# ArdNixie.net
KiCad netlist of a schematic drawn in EAGLE
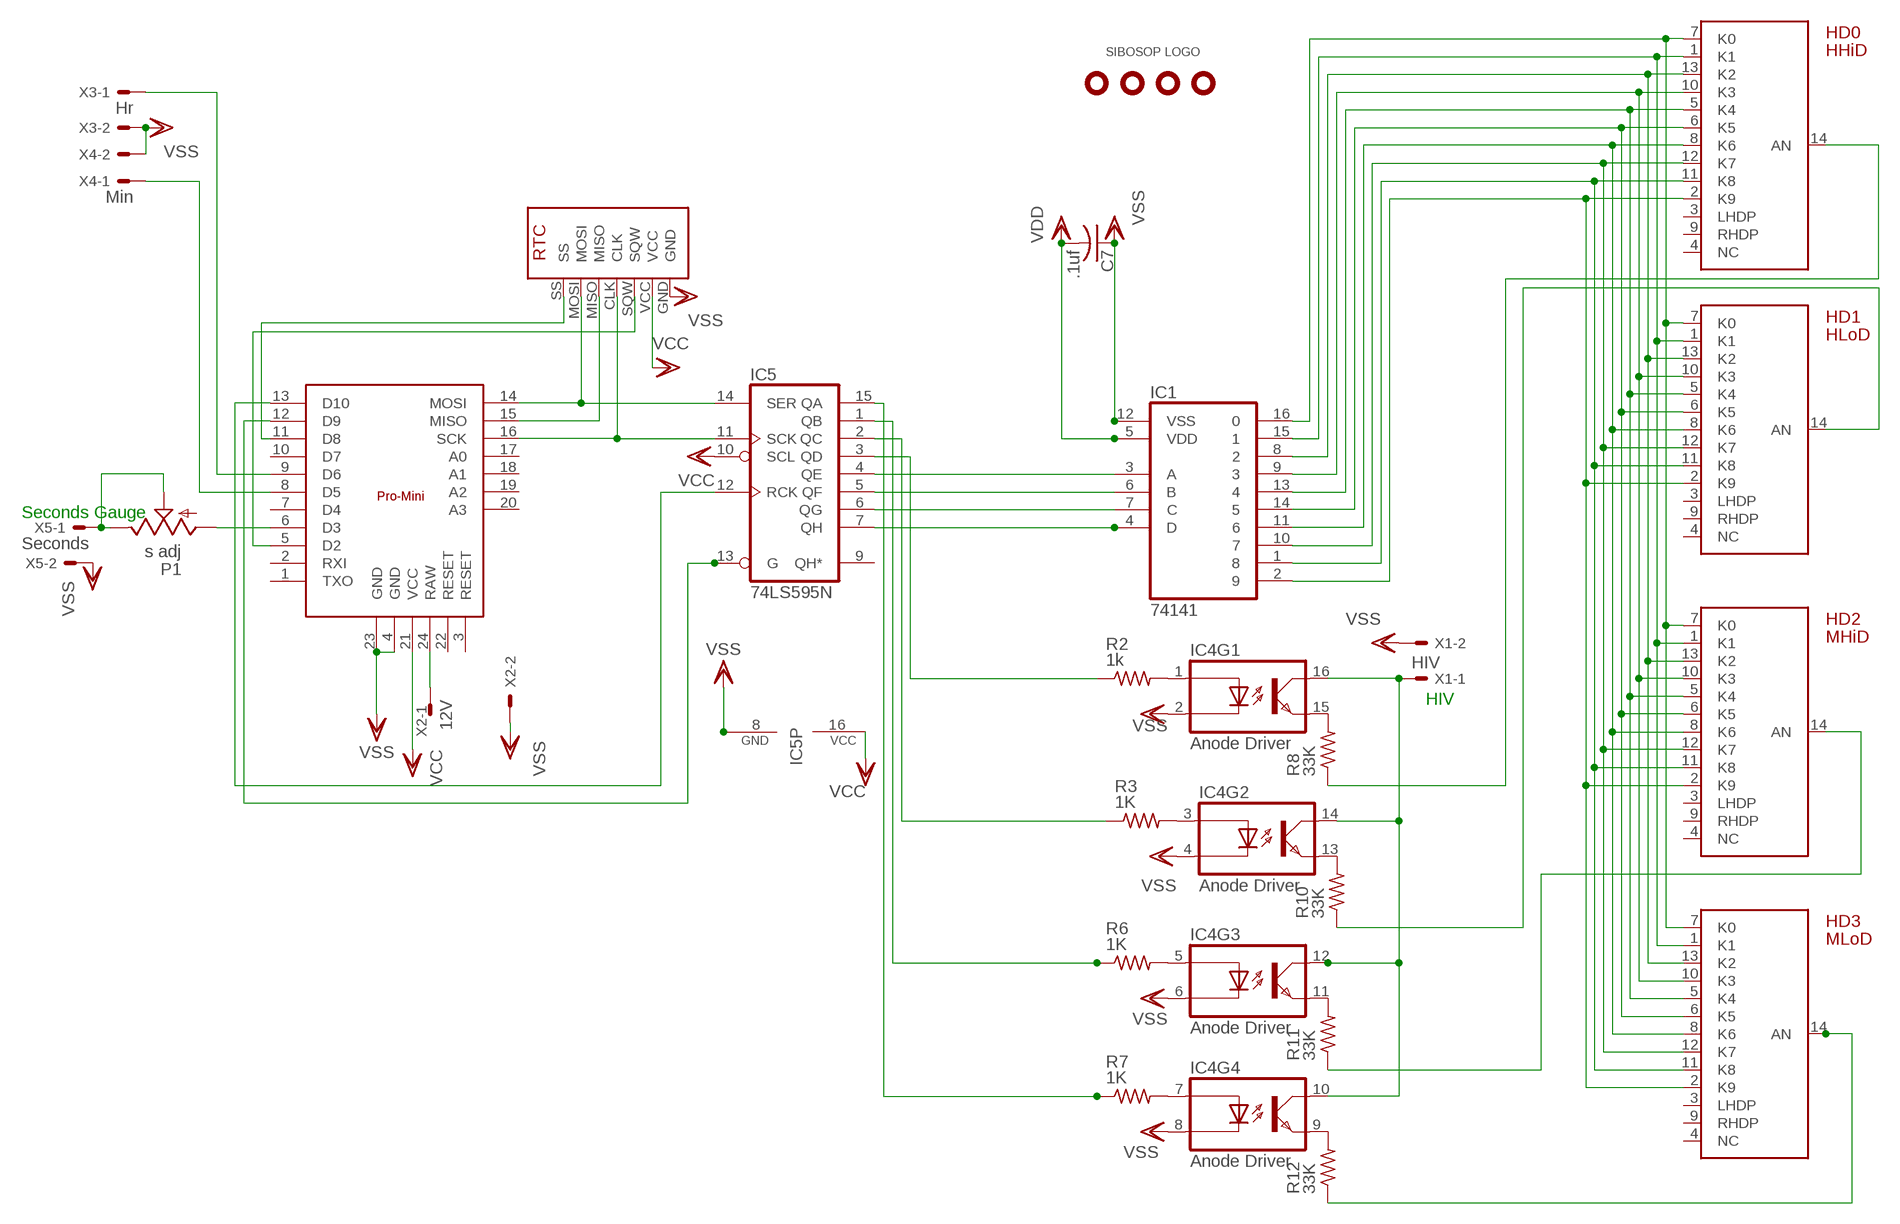
[diagram p0: schematic, sheet 1]

(export (version "E")
  (design (tool "Eeschema 10.0.6"))
  (components
    (comp (ref "C7")
      (value ".1uf")
      (footprint "eagle-import:C025-024X044")
      (libsource (lib "eagle-import") (part "C-US025-024X044"))
    )
    (comp (ref "HD0")
      (value "HHiD")
      (footprint "eagle-import:DIL14")
      (libsource (lib "eagle-import") (part "NIXIE-5440-HEADER"))
    )
    (comp (ref "HD1")
      (value "HLoD")
      (footprint "eagle-import:DIL14")
      (libsource (lib "eagle-import") (part "NIXIE-5440-HEADER"))
    )
    (comp (ref "HD2")
      (value "MHiD")
      (footprint "eagle-import:DIL14")
      (libsource (lib "eagle-import") (part "NIXIE-5440-HEADER"))
    )
    (comp (ref "HD3")
      (value "MLoD")
      (footprint "eagle-import:DIL14")
      (libsource (lib "eagle-import") (part "NIXIE-5440-HEADER"))
    )
    (comp (ref "IC1")
      (value "74141")
      (footprint "eagle-import:DIP16")
      (libsource (lib "eagle-import") (part "74141"))
    )
    (comp (ref "IC2")
      (value "PRO-MINI")
      (footprint "eagle-import:DIL24-6-EXT")
      (libsource (lib "eagle-import") (part "PRO-MINI"))
    )
    (comp (ref "IC3")
      (value "SPARKRTC")
      (footprint "eagle-import:SPARKRTC")
      (libsource (lib "eagle-import") (part "SPARKRTC"))
    )
    (comp (ref "IC4")
      (value "Anode Driver")
      (footprint "eagle-import:DIP16")
      (libsource (lib "eagle-import") (part "TLP627"))
    )
    (comp (ref "IC5")
      (value "74LS595N")
      (footprint "eagle-import:DIL16")
      (libsource (lib "eagle-import") (part "74595NLS"))
    )
    (comp (ref "P1")
      (value "s adj")
      (footprint "eagle-import:RJ6S")
      (libsource (lib "eagle-import") (part "TRIMPOT"))
    )
    (comp (ref "R2")
      (value "1k")
      (footprint "eagle-import:0204V")
      (libsource (lib "eagle-import") (part "R-US_0204/2V"))
    )
    (comp (ref "R3")
      (value "1K")
      (footprint "eagle-import:0204V")
      (libsource (lib "eagle-import") (part "R-US_0204/2V"))
    )
    (comp (ref "R6")
      (value "1K")
      (footprint "eagle-import:0204V")
      (libsource (lib "eagle-import") (part "R-US_0204/2V"))
    )
    (comp (ref "R7")
      (value "1K")
      (footprint "eagle-import:0204V")
      (libsource (lib "eagle-import") (part "R-US_0204/2V"))
    )
    (comp (ref "R8")
      (value "33K")
      (footprint "eagle-import:0204V")
      (libsource (lib "eagle-import") (part "R-US_0204/2V"))
    )
    (comp (ref "R10")
      (value "33K")
      (footprint "eagle-import:0204V")
      (libsource (lib "eagle-import") (part "R-US_0204/2V"))
    )
    (comp (ref "R11")
      (value "33K")
      (footprint "eagle-import:0204V")
      (libsource (lib "eagle-import") (part "R-US_0204/2V"))
    )
    (comp (ref "R12")
      (value "33K")
      (footprint "eagle-import:0204V")
      (libsource (lib "eagle-import") (part "R-US_0204/2V"))
    )
    (comp (ref "U$1")
      (value "HOLE-125")
      (footprint "eagle-import:HOLE-125")
      (libsource (lib "eagle-import") (part "HOLE-125"))
    )
    (comp (ref "U$2")
      (value "HOLE-125")
      (footprint "eagle-import:HOLE-125")
      (libsource (lib "eagle-import") (part "HOLE-125"))
    )
    (comp (ref "U$3")
      (value "LOGO")
      (footprint "eagle-import:LOGO")
      (libsource (lib "eagle-import") (part "LOGO"))
    )
    (comp (ref "U$5")
      (value "HOLE-125")
      (footprint "eagle-import:HOLE-125")
      (libsource (lib "eagle-import") (part "HOLE-125"))
    )
    (comp (ref "U$7")
      (value "HOLE-125")
      (footprint "eagle-import:HOLE-125")
      (libsource (lib "eagle-import") (part "HOLE-125"))
    )
    (comp (ref "X1")
      (value "HIV")
      (footprint "eagle-import:22-23-2021")
      (libsource (lib "eagle-import") (part "22-23-2021"))
    )
    (comp (ref "X2")
      (value "12V")
      (footprint "eagle-import:22-23-2021")
      (libsource (lib "eagle-import") (part "22-23-2021"))
    )
    (comp (ref "X3")
      (value "Hr")
      (footprint "eagle-import:22-23-2021")
      (libsource (lib "eagle-import") (part "22-23-2021"))
    )
    (comp (ref "X4")
      (value "Min")
      (footprint "eagle-import:22-23-2021")
      (libsource (lib "eagle-import") (part "22-23-2021"))
    )
    (comp (ref "X5")
      (value "Seconds")
      (footprint "eagle-import:22-23-2021")
      (libsource (lib "eagle-import") (part "22-23-2021"))
    )
  )
  (nets
    (net (code "1") (name "Net-(HD0-AN)") (class "Default")
      (node (ref "HD0") (pin "14") (pinfunction "AN_14") (pintype "passive"))
      (node (ref "R8") (pin "1") (pinfunction "1_1") (pintype "passive"))
    )
    (net (code "2") (name "Net-(HD0-K0)") (class "Default")
      (node (ref "HD0") (pin "7") (pinfunction "K0_7") (pintype "passive"))
      (node (ref "HD1") (pin "7") (pinfunction "K0_7") (pintype "passive"))
      (node (ref "HD2") (pin "7") (pinfunction "K0_7") (pintype "passive"))
      (node (ref "HD3") (pin "7") (pinfunction "K0_7") (pintype "passive"))
      (node (ref "IC1") (pin "16") (pinfunction "0_16") (pintype "open_collector"))
    )
    (net (code "3") (name "Net-(HD0-K1)") (class "Default")
      (node (ref "HD0") (pin "1") (pinfunction "K1_1") (pintype "passive"))
      (node (ref "HD1") (pin "1") (pinfunction "K1_1") (pintype "passive"))
      (node (ref "HD2") (pin "1") (pinfunction "K1_1") (pintype "passive"))
      (node (ref "HD3") (pin "1") (pinfunction "K1_1") (pintype "passive"))
      (node (ref "IC1") (pin "15") (pinfunction "1_15") (pintype "open_collector"))
    )
    (net (code "4") (name "Net-(HD0-K2)") (class "Default")
      (node (ref "HD0") (pin "13") (pinfunction "K2_13") (pintype "passive"))
      (node (ref "HD1") (pin "13") (pinfunction "K2_13") (pintype "passive"))
      (node (ref "HD2") (pin "13") (pinfunction "K2_13") (pintype "passive"))
      (node (ref "HD3") (pin "13") (pinfunction "K2_13") (pintype "passive"))
      (node (ref "IC1") (pin "8") (pinfunction "2_8") (pintype "open_collector"))
    )
    (net (code "5") (name "Net-(HD0-K3)") (class "Default")
      (node (ref "HD0") (pin "10") (pinfunction "K3_10") (pintype "passive"))
      (node (ref "HD1") (pin "10") (pinfunction "K3_10") (pintype "passive"))
      (node (ref "HD2") (pin "10") (pinfunction "K3_10") (pintype "passive"))
      (node (ref "HD3") (pin "10") (pinfunction "K3_10") (pintype "passive"))
      (node (ref "IC1") (pin "9") (pinfunction "3_9") (pintype "open_collector"))
    )
    (net (code "6") (name "Net-(HD0-K4)") (class "Default")
      (node (ref "HD0") (pin "5") (pinfunction "K4_5") (pintype "passive"))
      (node (ref "HD1") (pin "5") (pinfunction "K4_5") (pintype "passive"))
      (node (ref "HD2") (pin "5") (pinfunction "K4_5") (pintype "passive"))
      (node (ref "HD3") (pin "5") (pinfunction "K4_5") (pintype "passive"))
      (node (ref "IC1") (pin "13") (pinfunction "4_13") (pintype "open_collector"))
    )
    (net (code "7") (name "Net-(HD0-K5)") (class "Default")
      (node (ref "HD0") (pin "6") (pinfunction "K5_6") (pintype "passive"))
      (node (ref "HD1") (pin "6") (pinfunction "K5_6") (pintype "passive"))
      (node (ref "HD2") (pin "6") (pinfunction "K5_6") (pintype "passive"))
      (node (ref "HD3") (pin "6") (pinfunction "K5_6") (pintype "passive"))
      (node (ref "IC1") (pin "14") (pinfunction "5_14") (pintype "open_collector"))
    )
    (net (code "8") (name "Net-(HD0-K6)") (class "Default")
      (node (ref "HD0") (pin "8") (pinfunction "K6_8") (pintype "passive"))
      (node (ref "HD1") (pin "8") (pinfunction "K6_8") (pintype "passive"))
      (node (ref "HD2") (pin "8") (pinfunction "K6_8") (pintype "passive"))
      (node (ref "HD3") (pin "8") (pinfunction "K6_8") (pintype "passive"))
      (node (ref "IC1") (pin "11") (pinfunction "6_11") (pintype "open_collector"))
    )
    (net (code "9") (name "Net-(HD0-K7)") (class "Default")
      (node (ref "HD0") (pin "12") (pinfunction "K7_12") (pintype "passive"))
      (node (ref "HD1") (pin "12") (pinfunction "K7_12") (pintype "passive"))
      (node (ref "HD2") (pin "12") (pinfunction "K7_12") (pintype "passive"))
      (node (ref "HD3") (pin "12") (pinfunction "K7_12") (pintype "passive"))
      (node (ref "IC1") (pin "10") (pinfunction "7_10") (pintype "open_collector"))
    )
    (net (code "10") (name "Net-(HD0-K8)") (class "Default")
      (node (ref "HD0") (pin "11") (pinfunction "K8_11") (pintype "passive"))
      (node (ref "HD1") (pin "11") (pinfunction "K8_11") (pintype "passive"))
      (node (ref "HD2") (pin "11") (pinfunction "K8_11") (pintype "passive"))
      (node (ref "HD3") (pin "11") (pinfunction "K8_11") (pintype "passive"))
      (node (ref "IC1") (pin "1") (pinfunction "8_1") (pintype "open_collector"))
    )
    (net (code "11") (name "Net-(HD0-K9)") (class "Default")
      (node (ref "HD0") (pin "2") (pinfunction "K9_2") (pintype "passive"))
      (node (ref "HD1") (pin "2") (pinfunction "K9_2") (pintype "passive"))
      (node (ref "HD2") (pin "2") (pinfunction "K9_2") (pintype "passive"))
      (node (ref "HD3") (pin "2") (pinfunction "K9_2") (pintype "passive"))
      (node (ref "IC1") (pin "2") (pinfunction "9_2") (pintype "open_collector"))
    )
    (net (code "12") (name "Net-(HD1-AN)") (class "Default")
      (node (ref "HD1") (pin "14") (pinfunction "AN_14") (pintype "passive"))
      (node (ref "R10") (pin "1") (pinfunction "1_1") (pintype "passive"))
    )
    (net (code "13") (name "Net-(HD2-AN)") (class "Default")
      (node (ref "HD2") (pin "14") (pinfunction "AN_14") (pintype "passive"))
      (node (ref "R11") (pin "1") (pinfunction "1_1") (pintype "passive"))
    )
    (net (code "14") (name "Net-(HD3-AN)") (class "Default")
      (node (ref "HD3") (pin "14") (pinfunction "AN_14") (pintype "passive"))
      (node (ref "R12") (pin "1") (pinfunction "1_1") (pintype "passive"))
    )
    (net (code "15") (name "Net-(IC1-A)") (class "Default")
      (node (ref "IC1") (pin "3") (pinfunction "A_3") (pintype "input"))
      (node (ref "IC5") (pin "4") (pinfunction "QE_4") (pintype "tri_state"))
    )
    (net (code "16") (name "Net-(IC1-B)") (class "Default")
      (node (ref "IC1") (pin "6") (pinfunction "B_6") (pintype "input"))
      (node (ref "IC5") (pin "5") (pinfunction "QF_5") (pintype "tri_state"))
    )
    (net (code "17") (name "Net-(IC1-C)") (class "Default")
      (node (ref "IC1") (pin "7") (pinfunction "C_7") (pintype "input"))
      (node (ref "IC5") (pin "6") (pinfunction "QG_6") (pintype "tri_state"))
    )
    (net (code "18") (name "Net-(IC1-D)") (class "Default")
      (node (ref "IC1") (pin "4") (pinfunction "D_4") (pintype "input"))
      (node (ref "IC5") (pin "7") (pinfunction "QH_7") (pintype "tri_state"))
    )
    (net (code "19") (name "Net-(IC2-D2)") (class "Default")
      (node (ref "IC2") (pin "5") (pinfunction "D2_5") (pintype "bidirectional"))
      (node (ref "IC3") (pin "SQW") (pinfunction "SQW_SQW") (pintype "bidirectional"))
    )
    (net (code "20") (name "Net-(IC2-D3)") (class "Default")
      (node (ref "IC2") (pin "6") (pinfunction "D3_6") (pintype "bidirectional"))
      (node (ref "P1") (pin "A") (pinfunction "A_A") (pintype "passive"))
    )
    (net (code "21") (name "Net-(IC2-D5)") (class "Default")
      (node (ref "IC2") (pin "8") (pinfunction "D5_8") (pintype "bidirectional"))
      (node (ref "X4") (pin "1") (pinfunction "S_1") (pintype "passive"))
    )
    (net (code "22") (name "Net-(IC2-D6)") (class "Default")
      (node (ref "IC2") (pin "9") (pinfunction "D6_9") (pintype "bidirectional"))
      (node (ref "X3") (pin "1") (pinfunction "S_1") (pintype "passive"))
    )
    (net (code "23") (name "Net-(IC2-D8)") (class "Default")
      (node (ref "IC2") (pin "11") (pinfunction "D8_11") (pintype "bidirectional"))
      (node (ref "IC3") (pin "SS") (pinfunction "SS_SS") (pintype "bidirectional"))
    )
    (net (code "24") (name "Net-(IC2-D9)") (class "Default")
      (node (ref "IC2") (pin "12") (pinfunction "D9_12") (pintype "bidirectional"))
      (node (ref "IC5") (pin "13") (pinfunction "G_13") (pintype "input"))
    )
    (net (code "25") (name "Net-(IC2-D10)") (class "Default")
      (node (ref "IC2") (pin "13") (pinfunction "D10_13") (pintype "bidirectional"))
      (node (ref "IC5") (pin "12") (pinfunction "RCK_12") (pintype "input"))
    )
    (net (code "26") (name "Net-(IC2-MISO)") (class "Default")
      (node (ref "IC2") (pin "15") (pinfunction "MISO_15") (pintype "bidirectional"))
      (node (ref "IC3") (pin "MISO") (pinfunction "MISO_MISO") (pintype "bidirectional"))
    )
    (net (code "27") (name "Net-(IC2-MOSI)") (class "Default")
      (node (ref "IC2") (pin "14") (pinfunction "MOSI_14") (pintype "bidirectional"))
      (node (ref "IC3") (pin "MOSI") (pinfunction "MOSI_MOSI") (pintype "bidirectional"))
      (node (ref "IC5") (pin "14") (pinfunction "SER_14") (pintype "input"))
    )
    (net (code "28") (name "Net-(IC2-RAW)") (class "Default")
      (node (ref "IC2") (pin "24") (pinfunction "RAW_24") (pintype "power_in"))
      (node (ref "X2") (pin "1") (pinfunction "S_1") (pintype "passive"))
    )
    (net (code "29") (name "Net-(IC2-SCK)") (class "Default")
      (node (ref "IC2") (pin "16") (pinfunction "SCK_16") (pintype "bidirectional"))
      (node (ref "IC3") (pin "CLK") (pinfunction "CLK_CLK") (pintype "bidirectional"))
      (node (ref "IC5") (pin "11") (pinfunction "SCK_11") (pintype "input"))
    )
    (net (code "30") (name "Net-(IC4A-AN)") (class "Default")
      (node (ref "IC4") (pin "1") (pinfunction "AN_1") (pintype "passive"))
      (node (ref "R2") (pin "2") (pinfunction "2_2") (pintype "passive"))
    )
    (net (code "31") (name "Net-(IC4A-CO)") (class "Default")
      (node (ref "IC4") (pin "10") (pinfunction "CO_10") (pintype "passive"))
      (node (ref "IC4") (pin "12") (pinfunction "CO_12") (pintype "passive"))
      (node (ref "IC4") (pin "14") (pinfunction "CO_14") (pintype "passive"))
      (node (ref "IC4") (pin "16") (pinfunction "CO_16") (pintype "passive"))
      (node (ref "X1") (pin "1") (pinfunction "S_1") (pintype "passive"))
    )
    (net (code "32") (name "Net-(IC4A-EM)") (class "Default")
      (node (ref "IC4") (pin "15") (pinfunction "EM_15") (pintype "passive"))
      (node (ref "R8") (pin "2") (pinfunction "2_2") (pintype "passive"))
    )
    (net (code "33") (name "Net-(IC4B-AN)") (class "Default")
      (node (ref "IC4") (pin "3") (pinfunction "AN_3") (pintype "passive"))
      (node (ref "R3") (pin "2") (pinfunction "2_2") (pintype "passive"))
    )
    (net (code "34") (name "Net-(IC4B-EM)") (class "Default")
      (node (ref "IC4") (pin "13") (pinfunction "EM_13") (pintype "passive"))
      (node (ref "R10") (pin "2") (pinfunction "2_2") (pintype "passive"))
    )
    (net (code "35") (name "Net-(IC4C-AN)") (class "Default")
      (node (ref "IC4") (pin "5") (pinfunction "AN_5") (pintype "passive"))
      (node (ref "R6") (pin "2") (pinfunction "2_2") (pintype "passive"))
    )
    (net (code "36") (name "Net-(IC4C-EM)") (class "Default")
      (node (ref "IC4") (pin "11") (pinfunction "EM_11") (pintype "passive"))
      (node (ref "R11") (pin "2") (pinfunction "2_2") (pintype "passive"))
    )
    (net (code "37") (name "Net-(IC4D-AN)") (class "Default")
      (node (ref "IC4") (pin "7") (pinfunction "AN_7") (pintype "passive"))
      (node (ref "R7") (pin "2") (pinfunction "2_2") (pintype "passive"))
    )
    (net (code "38") (name "Net-(IC4D-EM)") (class "Default")
      (node (ref "IC4") (pin "9") (pinfunction "EM_9") (pintype "passive"))
      (node (ref "R12") (pin "2") (pinfunction "2_2") (pintype "passive"))
    )
    (net (code "39") (name "Net-(IC5A-QA)") (class "Default")
      (node (ref "IC5") (pin "15") (pinfunction "QA_15") (pintype "tri_state"))
      (node (ref "R7") (pin "1") (pinfunction "1_1") (pintype "passive"))
    )
    (net (code "40") (name "Net-(IC5A-QB)") (class "Default")
      (node (ref "IC5") (pin "1") (pinfunction "QB_1") (pintype "tri_state"))
      (node (ref "R6") (pin "1") (pinfunction "1_1") (pintype "passive"))
    )
    (net (code "41") (name "Net-(IC5A-QC)") (class "Default")
      (node (ref "IC5") (pin "2") (pinfunction "QC_2") (pintype "tri_state"))
      (node (ref "R3") (pin "1") (pinfunction "1_1") (pintype "passive"))
    )
    (net (code "42") (name "Net-(IC5A-QD)") (class "Default")
      (node (ref "IC5") (pin "3") (pinfunction "QD_3") (pintype "tri_state"))
      (node (ref "R2") (pin "1") (pinfunction "1_1") (pintype "passive"))
    )
    (net (code "43") (name "Net-(X5A-S)") (class "Default")
      (node (ref "P1") (pin "E") (pinfunction "E_E") (pintype "passive"))
      (node (ref "P1") (pin "S") (pinfunction "S_S") (pintype "passive"))
      (node (ref "X5") (pin "1") (pinfunction "S_1") (pintype "passive"))
    )
    (net (code "44") (name "VCC") (class "Default")
      (node (ref "C7") (pin "2") (pinfunction "2_2") (pintype "passive"))
      (node (ref "IC1") (pin "5") (pinfunction "VDD_5") (pintype "power_in"))
      (node (ref "IC2") (pin "21") (pinfunction "VCC_21") (pintype "power_in"))
      (node (ref "IC3") (pin "VCC") (pinfunction "VCC_VCC") (pintype "power_in"))
      (node (ref "IC5") (pin "10") (pinfunction "SCL_10") (pintype "input"))
      (node (ref "IC5") (pin "16") (pinfunction "VCC_16") (pintype "power_in"))
    )
    (net (code "45") (name "VSS") (class "Default")
      (node (ref "C7") (pin "1") (pinfunction "1_1") (pintype "passive"))
      (node (ref "IC1") (pin "12") (pinfunction "VSS_12") (pintype "power_in"))
      (node (ref "IC2") (pin "23") (pinfunction "GND_23") (pintype "bidirectional"))
      (node (ref "IC2") (pin "4") (pinfunction "GND_4") (pintype "power_in"))
      (node (ref "IC3") (pin "GND") (pinfunction "GND_GND") (pintype "power_in"))
      (node (ref "IC4") (pin "2") (pinfunction "CA_2") (pintype "passive"))
      (node (ref "IC4") (pin "4") (pinfunction "CA_4") (pintype "passive"))
      (node (ref "IC4") (pin "6") (pinfunction "CA_6") (pintype "passive"))
      (node (ref "IC4") (pin "8") (pinfunction "CA_8") (pintype "passive"))
      (node (ref "IC5") (pin "8") (pinfunction "GND_8") (pintype "power_in"))
      (node (ref "X1") (pin "2") (pinfunction "S_2") (pintype "passive"))
      (node (ref "X2") (pin "2") (pinfunction "S_2") (pintype "passive"))
      (node (ref "X3") (pin "2") (pinfunction "S_2") (pintype "passive"))
      (node (ref "X4") (pin "2") (pinfunction "S_2") (pintype "passive"))
      (node (ref "X5") (pin "2") (pinfunction "S_2") (pintype "passive"))
    )
    (net (code "46") (name "unconnected-(HD0-LHDP-Pad3)") (class "Default")
      (node (ref "HD0") (pin "3") (pinfunction "LHDP_3") (pintype "passive"))
    )
    (net (code "47") (name "unconnected-(HD0-NC-Pad4)") (class "Default")
      (node (ref "HD0") (pin "4") (pinfunction "NC_4") (pintype "passive"))
    )
    (net (code "48") (name "unconnected-(HD0-RHDP-Pad9)") (class "Default")
      (node (ref "HD0") (pin "9") (pinfunction "RHDP_9") (pintype "passive"))
    )
    (net (code "49") (name "unconnected-(HD1-LHDP-Pad3)") (class "Default")
      (node (ref "HD1") (pin "3") (pinfunction "LHDP_3") (pintype "passive"))
    )
    (net (code "50") (name "unconnected-(HD1-NC-Pad4)") (class "Default")
      (node (ref "HD1") (pin "4") (pinfunction "NC_4") (pintype "passive"))
    )
    (net (code "51") (name "unconnected-(HD1-RHDP-Pad9)") (class "Default")
      (node (ref "HD1") (pin "9") (pinfunction "RHDP_9") (pintype "passive"))
    )
    (net (code "52") (name "unconnected-(HD2-LHDP-Pad3)") (class "Default")
      (node (ref "HD2") (pin "3") (pinfunction "LHDP_3") (pintype "passive"))
    )
    (net (code "53") (name "unconnected-(HD2-NC-Pad4)") (class "Default")
      (node (ref "HD2") (pin "4") (pinfunction "NC_4") (pintype "passive"))
    )
    (net (code "54") (name "unconnected-(HD2-RHDP-Pad9)") (class "Default")
      (node (ref "HD2") (pin "9") (pinfunction "RHDP_9") (pintype "passive"))
    )
    (net (code "55") (name "unconnected-(HD3-LHDP-Pad3)") (class "Default")
      (node (ref "HD3") (pin "3") (pinfunction "LHDP_3") (pintype "passive"))
    )
    (net (code "56") (name "unconnected-(HD3-NC-Pad4)") (class "Default")
      (node (ref "HD3") (pin "4") (pinfunction "NC_4") (pintype "passive"))
    )
    (net (code "57") (name "unconnected-(HD3-RHDP-Pad9)") (class "Default")
      (node (ref "HD3") (pin "9") (pinfunction "RHDP_9") (pintype "passive"))
    )
    (net (code "58") (name "unconnected-(IC2-A0-Pad17)") (class "Default")
      (node (ref "IC2") (pin "17") (pinfunction "A0_17") (pintype "bidirectional"))
    )
    (net (code "59") (name "unconnected-(IC2-A1-Pad18)") (class "Default")
      (node (ref "IC2") (pin "18") (pinfunction "A1_18") (pintype "bidirectional"))
    )
    (net (code "60") (name "unconnected-(IC2-A2-Pad19)") (class "Default")
      (node (ref "IC2") (pin "19") (pinfunction "A2_19") (pintype "bidirectional"))
    )
    (net (code "61") (name "unconnected-(IC2-A3-Pad20)") (class "Default")
      (node (ref "IC2") (pin "20") (pinfunction "A3_20") (pintype "bidirectional"))
    )
    (net (code "62") (name "unconnected-(IC2-D4-Pad7)") (class "Default")
      (node (ref "IC2") (pin "7") (pinfunction "D4_7") (pintype "bidirectional"))
    )
    (net (code "63") (name "unconnected-(IC2-D7-Pad10)") (class "Default")
      (node (ref "IC2") (pin "10") (pinfunction "D7_10") (pintype "bidirectional"))
    )
    (net (code "64") (name "unconnected-(IC2-RESET-Pad3)") (class "Default")
      (node (ref "IC2") (pin "3") (pinfunction "RESET_3") (pintype "input"))
    )
    (net (code "65") (name "unconnected-(IC2-RESET-Pad22)") (class "Default")
      (node (ref "IC2") (pin "22") (pinfunction "RESET_22") (pintype "bidirectional"))
    )
    (net (code "66") (name "unconnected-(IC2-RXI-Pad2)") (class "Default")
      (node (ref "IC2") (pin "2") (pinfunction "RXI_2") (pintype "input"))
    )
    (net (code "67") (name "unconnected-(IC2-TXO-Pad1)") (class "Default")
      (node (ref "IC2") (pin "1") (pinfunction "TXO_1") (pintype "output"))
    )
    (net (code "68") (name "unconnected-(IC5A-QH*-Pad9)") (class "Default")
      (node (ref "IC5") (pin "9") (pinfunction "QH*_9") (pintype "tri_state"))
    )
  )
)
